# DAC_MIC.net
KiCad netlist of a schematic drawn in Altium Designer
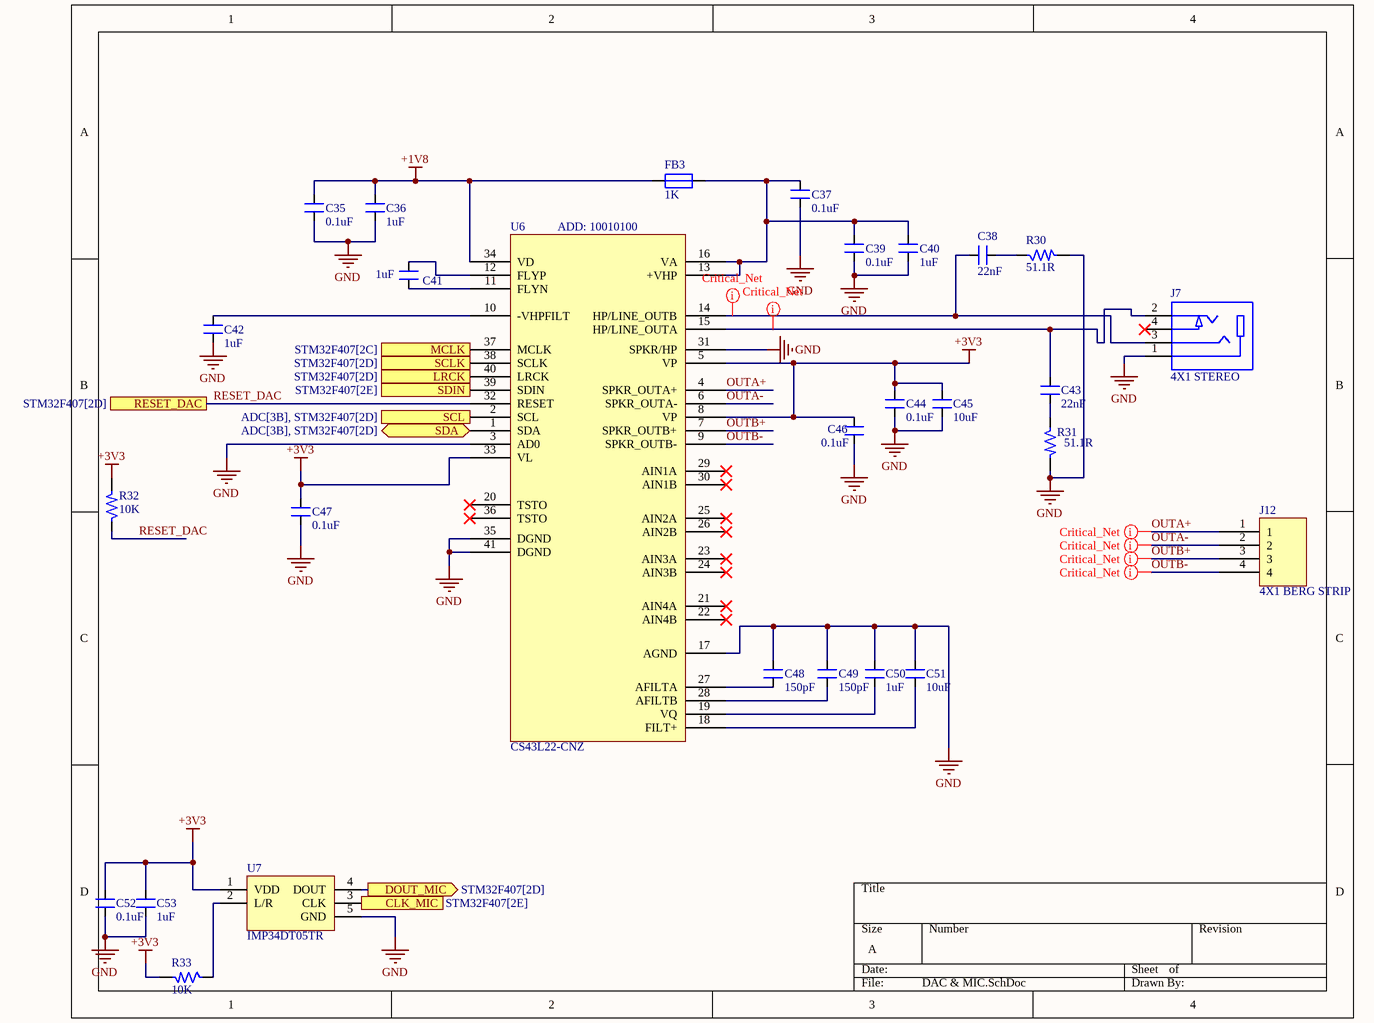
[diagram p0: DAC & MIC.SchDoc]

(export (version "E")
  (design (tool "Eeschema 10.0.6"))
  (components
    (comp (ref "C35")
      (value "0.1uF")
      (footprint "CAP_0805")
      (description "0.1µF ±10% 50V Ceramic Capacitor X7R 0805 (2012 Metric)")
      (fields
        (field (name "MANUFACTURER") "Samsung")
        (field (name "MANUFACTURER PART NUMBER") "CL21B104KBCNNNC")
      )
      (libsource (lib "ESTEEMPCBLIB") (part "CAP_0.1uF-50V-10%-0805"))
    )
    (comp (ref "C36")
      (value "1uF")
      (footprint "CAP_0805")
      (description "1µF ±5% 50V Ceramic Capacitor X7R 0805 (2012 Metric)")
      (fields
        (field (name "MANUFACTURER") "Samsung")
        (field (name "MANUFACTURER PART NUMBER") "CC0805JKX7R9BB105")
      )
      (libsource (lib "ESTEEMPCBLIB") (part "CAP_1uF-50V-5%-0805"))
    )
    (comp (ref "C37")
      (value "0.1uF")
      (footprint "CAP_0805")
      (description "0.1µF ±10% 50V Ceramic Capacitor X7R 0805 (2012 Metric)")
      (fields
        (field (name "MANUFACTURER") "Samsung")
        (field (name "MANUFACTURER PART NUMBER") "CL21B104KBCNNNC")
      )
      (libsource (lib "ESTEEMPCBLIB") (part "CAP_0.1uF-50V-10%-0805"))
    )
    (comp (ref "C38")
      (value "22nF")
      (footprint "CAP_0805")
      (description "0.022µF ±10% 50V Ceramic Capacitor X7R 0805 (2012 Metric)")
      (fields
        (field (name "MANUFACTURER") "Samsung Electro-Mechanics")
        (field (name "MANUFACTURER PART NUMBER") "CL21B223KBANNNC")
      )
      (libsource (lib "ESTEEMPCBLIB") (part "CAP_22nF-50V-10%-0805"))
    )
    (comp (ref "C39")
      (value "0.1uF")
      (footprint "CAP_0805")
      (description "0.1µF ±10% 50V Ceramic Capacitor X7R 0805 (2012 Metric)")
      (fields
        (field (name "MANUFACTURER") "Samsung")
        (field (name "MANUFACTURER PART NUMBER") "CL21B104KBCNNNC")
      )
      (libsource (lib "ESTEEMPCBLIB") (part "CAP_0.1uF-50V-10%-0805"))
    )
    (comp (ref "C40")
      (value "1uF")
      (footprint "CAP_0805")
      (description "1µF ±5% 50V Ceramic Capacitor X7R 0805 (2012 Metric)")
      (fields
        (field (name "MANUFACTURER") "Samsung")
        (field (name "MANUFACTURER PART NUMBER") "CC0805JKX7R9BB105")
      )
      (libsource (lib "ESTEEMPCBLIB") (part "CAP_1uF-50V-5%-0805"))
    )
    (comp (ref "C41")
      (value "1uF")
      (footprint "CAP_0805")
      (description "1µF ±5% 50V Ceramic Capacitor X7R 0805 (2012 Metric)")
      (fields
        (field (name "MANUFACTURER") "Samsung")
        (field (name "MANUFACTURER PART NUMBER") "CC0805JKX7R9BB105")
      )
      (libsource (lib "ESTEEMPCBLIB") (part "CAP_1uF-50V-5%-0805"))
    )
    (comp (ref "C42")
      (value "1uF")
      (footprint "CAP_0805")
      (description "1µF ±5% 50V Ceramic Capacitor X7R 0805 (2012 Metric)")
      (fields
        (field (name "MANUFACTURER") "Samsung")
        (field (name "MANUFACTURER PART NUMBER") "CC0805JKX7R9BB105")
      )
      (libsource (lib "ESTEEMPCBLIB") (part "CAP_1uF-50V-5%-0805"))
    )
    (comp (ref "C43")
      (value "22nF")
      (footprint "CAP_0805")
      (description "0.022µF ±10% 50V Ceramic Capacitor X7R 0805 (2012 Metric)")
      (fields
        (field (name "MANUFACTURER") "Samsung Electro-Mechanics")
        (field (name "MANUFACTURER PART NUMBER") "CL21B223KBANNNC")
      )
      (libsource (lib "ESTEEMPCBLIB") (part "CAP_22nF-50V-10%-0805"))
    )
    (comp (ref "C44")
      (value "0.1uF")
      (footprint "CAP_0805")
      (description "0.1µF ±10% 50V Ceramic Capacitor X7R 0805 (2012 Metric)")
      (fields
        (field (name "MANUFACTURER") "Samsung")
        (field (name "MANUFACTURER PART NUMBER") "CL21B104KBCNNNC")
      )
      (libsource (lib "ESTEEMPCBLIB") (part "CAP_0.1uF-50V-10%-0805"))
    )
    (comp (ref "C45")
      (value "10uF")
      (footprint "CAP_1206")
      (description "10µF ±10% 50V Ceramic Capacitor X7R 1206 (3216 Metric)")
      (fields
        (field (name "MANUFACTURER") "KEMET")
        (field (name "MANUFACTURER PART NUMBER") "CL31B106KBHNNNE")
      )
      (libsource (lib "ESTEEMPCBLIB") (part "CAP_10uF-50V-10%-1206"))
    )
    (comp (ref "C46")
      (value "0.1uF")
      (footprint "CAP_0805")
      (description "0.1µF ±10% 50V Ceramic Capacitor X7R 0805 (2012 Metric)")
      (fields
        (field (name "MANUFACTURER") "Samsung")
        (field (name "MANUFACTURER PART NUMBER") "CL21B104KBCNNNC")
      )
      (libsource (lib "ESTEEMPCBLIB") (part "CAP_0.1uF-50V-10%-0805"))
    )
    (comp (ref "C47")
      (value "0.1uF")
      (footprint "CAP_0805")
      (description "0.1µF ±10% 50V Ceramic Capacitor X7R 0805 (2012 Metric)")
      (fields
        (field (name "MANUFACTURER") "Samsung")
        (field (name "MANUFACTURER PART NUMBER") "CL21B104KBCNNNC")
      )
      (libsource (lib "ESTEEMPCBLIB") (part "CAP_0.1uF-50V-10%-0805"))
    )
    (comp (ref "C48")
      (value "150pF")
      (footprint "CAP_0805")
      (description "150pF ±10% 50V Ceramic Capacitor C0G, NP0 0805 (2012 Metric)")
      (fields
        (field (name "MANUFACTURER") "AVX Corporation")
        (field (name "MANUFACTURER PART NUMBER") "08055A151KAT2A")
      )
      (libsource (lib "ESTEEMPCBLIB") (part "CAP_150pF-50V-10%-0805"))
    )
    (comp (ref "C49")
      (value "150pF")
      (footprint "CAP_0805")
      (description "150pF ±10% 50V Ceramic Capacitor C0G, NP0 0805 (2012 Metric)")
      (fields
        (field (name "MANUFACTURER") "AVX Corporation")
        (field (name "MANUFACTURER PART NUMBER") "08055A151KAT2A")
      )
      (libsource (lib "ESTEEMPCBLIB") (part "CAP_150pF-50V-10%-0805"))
    )
    (comp (ref "C50")
      (value "1uF")
      (footprint "CAP_0805")
      (description "1µF ±5% 50V Ceramic Capacitor X7R 0805 (2012 Metric)")
      (fields
        (field (name "MANUFACTURER") "Samsung")
        (field (name "MANUFACTURER PART NUMBER") "CC0805JKX7R9BB105")
      )
      (libsource (lib "ESTEEMPCBLIB") (part "CAP_1uF-50V-5%-0805"))
    )
    (comp (ref "C51")
      (value "10uF")
      (footprint "CAP_1206")
      (description "10µF ±10% 50V Ceramic Capacitor X7R 1206 (3216 Metric)")
      (fields
        (field (name "MANUFACTURER") "KEMET")
        (field (name "MANUFACTURER PART NUMBER") "CL31B106KBHNNNE")
      )
      (libsource (lib "ESTEEMPCBLIB") (part "CAP_10uF-50V-10%-1206"))
    )
    (comp (ref "C52")
      (value "0.1uF")
      (footprint "CAP_0805")
      (description "0.1µF ±10% 50V Ceramic Capacitor X7R 0805 (2012 Metric)")
      (fields
        (field (name "MANUFACTURER") "Samsung")
        (field (name "MANUFACTURER PART NUMBER") "CL21B104KBCNNNC")
      )
      (libsource (lib "ESTEEMPCBLIB") (part "CAP_0.1uF-50V-10%-0805"))
    )
    (comp (ref "C53")
      (value "1uF")
      (footprint "CAP_0805")
      (description "1µF ±5% 50V Ceramic Capacitor X7R 0805 (2012 Metric)")
      (fields
        (field (name "MANUFACTURER") "Samsung")
        (field (name "MANUFACTURER PART NUMBER") "CC0805JKX7R9BB105")
      )
      (libsource (lib "ESTEEMPCBLIB") (part "CAP_1uF-50V-5%-0805"))
    )
    (comp (ref "FB3")
      (value "1K")
      (footprint "IND_0805")
      (description "1 kOhms @ 100MHz 1 Power Line Ferrite Bead 0805 (2012 Metric) 1.6A")
      (fields
        (field (name "MANUFACTURER") "Laird")
        (field (name "MANUFACTURER PART NUMBER") "BLM21SP102SH1D")
      )
      (libsource (lib "ESTEEMPCBLIB") (part "FB_1K-100MHZ-1.6A-0805"))
    )
    (comp (ref "J7")
      (value "4X1 STEREO")
      (footprint "CON_SJ-2504A-SMT-TR_SMD")
      (fields
        (field (name "MANUFACTURER") "CUI Devices")
        (field (name "MANUFACTURER PART NUMBER") "SJ-2504A-SMT-TR")
      )
      (libsource (lib "ESTEEMPCBLIB") (part "CON-PLG-STEREO_4X1-100-RA-SMD"))
    )
    (comp (ref "J12")
      (value "4X1 BERG STRIP")
      (footprint "CON4_100_40D72_TH_ST_MALE")
      (description "4 Pins, 1 Row 2.54mm Pitch, Straight bergstrip, Male")
      (fields (field (name "MANUFACTURER") "NA"))
      (libsource (lib "ESTEEMPCBLIB") (part "CON-BS-PLG_4X1-100-ST-TH"))
    )
    (comp (ref "R30")
      (value "51.1R")
      (footprint "RES_0603")
      (description "51.1 Ohms ±1% 0.1W, 1/10W Chip Resistor 0603 (1608 Metric) Thick Film")
      (fields
        (field (name "MANUFACTURER") "Vishay Dale")
        (field (name "MANUFACTURER PART NUMBER") "CRCW060351R1FKEAC")
      )
      (libsource (lib "ESTEEMPCBLIB") (part "RES_51.1R-0.1W-1%-0603"))
    )
    (comp (ref "R31")
      (value "51.1R")
      (footprint "RES_0603")
      (description "51.1 Ohms ±1% 0.1W, 1/10W Chip Resistor 0603 (1608 Metric) Thick Film")
      (fields
        (field (name "MANUFACTURER") "Vishay Dale")
        (field (name "MANUFACTURER PART NUMBER") "CRCW060351R1FKEAC")
      )
      (libsource (lib "ESTEEMPCBLIB") (part "RES_51.1R-0.1W-1%-0603"))
    )
    (comp (ref "R32")
      (value "10K")
      (footprint "RES_0603")
      (description "10 kOhms ±1% 0.1W, 1/10W Chip Resistor 0603 (1608 Metric) Automotive AEC-Q200 Thick Film")
      (fields (field (name "MANUFACTURER") "Walsin") (field (name "MANUFACTURER PART NUMBER") "WR06X1002FTL"))
      (libsource (lib "ESTEEMPCBLIB") (part "RES_10K-0.1W-1%-0603"))
    )
    (comp (ref "R33")
      (value "10K")
      (footprint "RES_0603")
      (description "10 kOhms ±1% 0.1W, 1/10W Chip Resistor 0603 (1608 Metric) Automotive AEC-Q200 Thick Film")
      (fields (field (name "MANUFACTURER") "Walsin") (field (name "MANUFACTURER PART NUMBER") "WR06X1002FTL"))
      (libsource (lib "ESTEEMPCBLIB") (part "RES_10K-0.1W-1%-0603"))
    )
    (comp (ref "U6")
      (value "CS43L22-CNZ")
      (footprint "QFN40_19_284_33X9_SMD")
      (description "Audio D/A Converter ICs Low Power Stereo DAC w/ClassD Spkr Driver")
      (fields (field (name "MANUFACTURER") "Cirrus Logic"))
      (libsource (lib "ESTEEMPCBLIB") (part "IC_CS43L22"))
    )
    (comp (ref "U7")
      (value "IMP34DT05TR")
      (footprint "HCLGA-4_53_137_15X37_SMD")
      (description "MEMS Microphones AUTO & INDUSTRIAL SENSORS")
      (fields (field (name "MANUFACTURER") "STMicroelectronics"))
      (libsource (lib "ESTEEMPCBLIB") (part "IC_IMP34DT05TR"))
    )
  )
  (nets
    (net (code "1") (name "+1V8") (class "Default")
      (node (ref "C35") (pin "2") (pinfunction "2_2") (pintype "passive"))
      (node (ref "C36") (pin "2") (pinfunction "2_2") (pintype "passive"))
      (node (ref "FB3") (pin "1") (pinfunction "1_1") (pintype "passive"))
      (node (ref "U6") (pin "34") (pinfunction "VD_34") (pintype "passive"))
    )
    (net (code "2") (name "+3V3") (class "Default")
      (node (ref "C44") (pin "2") (pinfunction "2_2") (pintype "passive"))
      (node (ref "C45") (pin "2") (pinfunction "2_2") (pintype "passive"))
      (node (ref "C46") (pin "2") (pinfunction "2_2") (pintype "passive"))
      (node (ref "C47") (pin "2") (pinfunction "2_2") (pintype "passive"))
      (node (ref "C52") (pin "2") (pinfunction "2_2") (pintype "passive"))
      (node (ref "C53") (pin "2") (pinfunction "2_2") (pintype "passive"))
      (node (ref "R32") (pin "2") (pinfunction "2_2") (pintype "passive"))
      (node (ref "R33") (pin "2") (pinfunction "2_2") (pintype "passive"))
      (node (ref "U6") (pin "33") (pinfunction "VL_33") (pintype "passive"))
      (node (ref "U6") (pin "5") (pinfunction "VP_5") (pintype "passive"))
      (node (ref "U6") (pin "8") (pinfunction "VP_8") (pintype "passive"))
      (node (ref "U7") (pin "1") (pinfunction "VDD_1") (pintype "passive"))
    )
    (net (code "3") (name "/CLK_MIC") (class "Default")
      (node (ref "U7") (pin "3") (pinfunction "CLK_3") (pintype "passive"))
    )
    (net (code "4") (name "/DOUT_MIC") (class "Default")
      (node (ref "U7") (pin "4") (pinfunction "DOUT_4") (pintype "passive"))
    )
    (net (code "5") (name "/LRCK") (class "Default")
      (node (ref "U6") (pin "40") (pinfunction "LRCK_40") (pintype "passive"))
    )
    (net (code "6") (name "/MCLK") (class "Default")
      (node (ref "U6") (pin "37") (pinfunction "MCLK_37") (pintype "passive"))
    )
    (net (code "7") (name "/OUTA+") (class "Default")
      (node (ref "J12") (pin "1") (pinfunction "1_1") (pintype "passive"))
      (node (ref "U6") (pin "4") (pinfunction "SPKR_OUTA+_4") (pintype "passive"))
    )
    (net (code "8") (name "/OUTA-") (class "Default")
      (node (ref "J12") (pin "2") (pinfunction "2_2") (pintype "passive"))
      (node (ref "U6") (pin "6") (pinfunction "SPKR_OUTA-_6") (pintype "passive"))
    )
    (net (code "9") (name "/OUTB+") (class "Default")
      (node (ref "J12") (pin "3") (pinfunction "3_3") (pintype "passive"))
      (node (ref "U6") (pin "7") (pinfunction "SPKR_OUTB+_7") (pintype "passive"))
    )
    (net (code "10") (name "/OUTB-") (class "Default")
      (node (ref "J12") (pin "4") (pinfunction "4_4") (pintype "passive"))
      (node (ref "U6") (pin "9") (pinfunction "SPKR_OUTB-_9") (pintype "passive"))
    )
    (net (code "11") (name "/RESET_DAC") (class "Default")
      (node (ref "R32") (pin "1") (pinfunction "1_1") (pintype "passive"))
      (node (ref "U6") (pin "32") (pinfunction "RESET_32") (pintype "passive"))
    )
    (net (code "12") (name "/SCL") (class "Default")
      (node (ref "U6") (pin "2") (pinfunction "SCL_2") (pintype "passive"))
    )
    (net (code "13") (name "/SCLK") (class "Default")
      (node (ref "U6") (pin "38") (pinfunction "SCLK_38") (pintype "passive"))
    )
    (net (code "14") (name "/SDA") (class "Default")
      (node (ref "U6") (pin "1") (pinfunction "SDA_1") (pintype "passive"))
    )
    (net (code "15") (name "/SDIN") (class "Default")
      (node (ref "U6") (pin "39") (pinfunction "SDIN_39") (pintype "passive"))
    )
    (net (code "16") (name "GND") (class "Default")
      (node (ref "C35") (pin "1") (pinfunction "1_1") (pintype "passive"))
      (node (ref "C36") (pin "1") (pinfunction "1_1") (pintype "passive"))
      (node (ref "C37") (pin "1") (pinfunction "1_1") (pintype "passive"))
      (node (ref "C39") (pin "1") (pinfunction "1_1") (pintype "passive"))
      (node (ref "C40") (pin "1") (pinfunction "1_1") (pintype "passive"))
      (node (ref "C42") (pin "1") (pinfunction "1_1") (pintype "passive"))
      (node (ref "C44") (pin "1") (pinfunction "1_1") (pintype "passive"))
      (node (ref "C45") (pin "1") (pinfunction "1_1") (pintype "passive"))
      (node (ref "C46") (pin "1") (pinfunction "1_1") (pintype "passive"))
      (node (ref "C47") (pin "1") (pinfunction "1_1") (pintype "passive"))
      (node (ref "C48") (pin "2") (pinfunction "2_2") (pintype "passive"))
      (node (ref "C49") (pin "2") (pinfunction "2_2") (pintype "passive"))
      (node (ref "C50") (pin "2") (pinfunction "2_2") (pintype "passive"))
      (node (ref "C51") (pin "2") (pinfunction "2_2") (pintype "passive"))
      (node (ref "C52") (pin "1") (pinfunction "1_1") (pintype "passive"))
      (node (ref "C53") (pin "1") (pinfunction "1_1") (pintype "passive"))
      (node (ref "J7") (pin "1") (pinfunction "1_1") (pintype "passive"))
      (node (ref "R30") (pin "2") (pinfunction "2_2") (pintype "passive"))
      (node (ref "R31") (pin "2") (pinfunction "2_2") (pintype "passive"))
      (node (ref "U6") (pin "17") (pinfunction "AGND_17") (pintype "passive"))
      (node (ref "U6") (pin "3") (pinfunction "AD0_3") (pintype "passive"))
      (node (ref "U6") (pin "31") (pinfunction "SPKR/HP_31") (pintype "passive"))
      (node (ref "U6") (pin "35") (pinfunction "DGND_35") (pintype "passive"))
      (node (ref "U6") (pin "41") (pinfunction "DGND_41") (pintype "passive"))
      (node (ref "U7") (pin "5") (pinfunction "GND_5") (pintype "passive"))
    )
    (net (code "17") (name "Net-(C38-Pad2)") (class "Default")
      (node (ref "C38") (pin "2") (pinfunction "2_2") (pintype "passive"))
      (node (ref "R30") (pin "1") (pinfunction "1_1") (pintype "passive"))
    )
    (net (code "18") (name "Net-(C43-Pad1)") (class "Default")
      (node (ref "C43") (pin "1") (pinfunction "1_1") (pintype "passive"))
      (node (ref "R31") (pin "1") (pinfunction "1_1") (pintype "passive"))
    )
    (net (code "19") (name "Net-(U6-+VHP)") (class "Default")
      (node (ref "C37") (pin "2") (pinfunction "2_2") (pintype "passive"))
      (node (ref "C39") (pin "2") (pinfunction "2_2") (pintype "passive"))
      (node (ref "C40") (pin "2") (pinfunction "2_2") (pintype "passive"))
      (node (ref "FB3") (pin "2") (pinfunction "2_2") (pintype "passive"))
      (node (ref "U6") (pin "13") (pinfunction "+VHP_13") (pintype "passive"))
      (node (ref "U6") (pin "16") (pinfunction "VA_16") (pintype "passive"))
    )
    (net (code "20") (name "Net-(U6--VHPFILT)") (class "Default")
      (node (ref "C42") (pin "2") (pinfunction "2_2") (pintype "passive"))
      (node (ref "U6") (pin "10") (pinfunction "-VHPFILT_10") (pintype "passive"))
    )
    (net (code "21") (name "Net-(U6-AFILTA)") (class "Default")
      (node (ref "C48") (pin "1") (pinfunction "1_1") (pintype "passive"))
      (node (ref "U6") (pin "27") (pinfunction "AFILTA_27") (pintype "passive"))
    )
    (net (code "22") (name "Net-(U6-AFILTB)") (class "Default")
      (node (ref "C49") (pin "1") (pinfunction "1_1") (pintype "passive"))
      (node (ref "U6") (pin "28") (pinfunction "AFILTB_28") (pintype "passive"))
    )
    (net (code "23") (name "Net-(U6-FILT+)") (class "Default")
      (node (ref "C51") (pin "1") (pinfunction "1_1") (pintype "passive"))
      (node (ref "U6") (pin "18") (pinfunction "FILT+_18") (pintype "passive"))
    )
    (net (code "24") (name "Net-(U6-FLYN)") (class "Default")
      (node (ref "C41") (pin "1") (pinfunction "1_1") (pintype "passive"))
      (node (ref "U6") (pin "11") (pinfunction "FLYN_11") (pintype "passive"))
    )
    (net (code "25") (name "Net-(U6-FLYP)") (class "Default")
      (node (ref "C41") (pin "2") (pinfunction "2_2") (pintype "passive"))
      (node (ref "U6") (pin "12") (pinfunction "FLYP_12") (pintype "passive"))
    )
    (net (code "26") (name "Net-(U6-HP{slash}LINE_OUTA)") (class "Default")
      (node (ref "C43") (pin "2") (pinfunction "2_2") (pintype "passive"))
      (node (ref "J7") (pin "2") (pinfunction "2_2") (pintype "passive"))
      (node (ref "U6") (pin "15") (pinfunction "HP/LINE_OUTA_15") (pintype "passive"))
    )
    (net (code "27") (name "Net-(U6-HP{slash}LINE_OUTB)") (class "Default")
      (node (ref "C38") (pin "1") (pinfunction "1_1") (pintype "passive"))
      (node (ref "J7") (pin "3") (pinfunction "3_3") (pintype "passive"))
      (node (ref "U6") (pin "14") (pinfunction "HP/LINE_OUTB_14") (pintype "passive"))
    )
    (net (code "28") (name "Net-(U6-VQ)") (class "Default")
      (node (ref "C50") (pin "1") (pinfunction "1_1") (pintype "passive"))
      (node (ref "U6") (pin "19") (pinfunction "VQ_19") (pintype "passive"))
    )
    (net (code "29") (name "Net-(U7-L{slash}R)") (class "Default")
      (node (ref "R33") (pin "1") (pinfunction "1_1") (pintype "passive"))
      (node (ref "U7") (pin "2") (pinfunction "L/R_2") (pintype "passive"))
    )
    (net (code "30") (name "unconnected-(J7-Pad4)") (class "Default")
      (node (ref "J7") (pin "4") (pinfunction "4_4") (pintype "passive+no_connect"))
    )
    (net (code "31") (name "unconnected-(U6-AIN1A-Pad29)") (class "Default")
      (node (ref "U6") (pin "29") (pinfunction "AIN1A_29") (pintype "passive+no_connect"))
    )
    (net (code "32") (name "unconnected-(U6-AIN1B-Pad30)") (class "Default")
      (node (ref "U6") (pin "30") (pinfunction "AIN1B_30") (pintype "passive+no_connect"))
    )
    (net (code "33") (name "unconnected-(U6-AIN2A-Pad25)") (class "Default")
      (node (ref "U6") (pin "25") (pinfunction "AIN2A_25") (pintype "passive+no_connect"))
    )
    (net (code "34") (name "unconnected-(U6-AIN2B-Pad26)") (class "Default")
      (node (ref "U6") (pin "26") (pinfunction "AIN2B_26") (pintype "passive+no_connect"))
    )
    (net (code "35") (name "unconnected-(U6-AIN3A-Pad23)") (class "Default")
      (node (ref "U6") (pin "23") (pinfunction "AIN3A_23") (pintype "passive+no_connect"))
    )
    (net (code "36") (name "unconnected-(U6-AIN3B-Pad24)") (class "Default")
      (node (ref "U6") (pin "24") (pinfunction "AIN3B_24") (pintype "passive+no_connect"))
    )
    (net (code "37") (name "unconnected-(U6-AIN4A-Pad21)") (class "Default")
      (node (ref "U6") (pin "21") (pinfunction "AIN4A_21") (pintype "passive+no_connect"))
    )
    (net (code "38") (name "unconnected-(U6-AIN4B-Pad22)") (class "Default")
      (node (ref "U6") (pin "22") (pinfunction "AIN4B_22") (pintype "passive+no_connect"))
    )
    (net (code "39") (name "unconnected-(U6-TSTO-Pad20)") (class "Default")
      (node (ref "U6") (pin "20") (pinfunction "TSTO_20") (pintype "passive+no_connect"))
    )
    (net (code "40") (name "unconnected-(U6-TSTO-Pad36)") (class "Default")
      (node (ref "U6") (pin "36") (pinfunction "TSTO_36") (pintype "passive+no_connect"))
    )
  )
)
